# Audio_input_ADC.net
KiCad netlist of a schematic drawn in Altium Designer
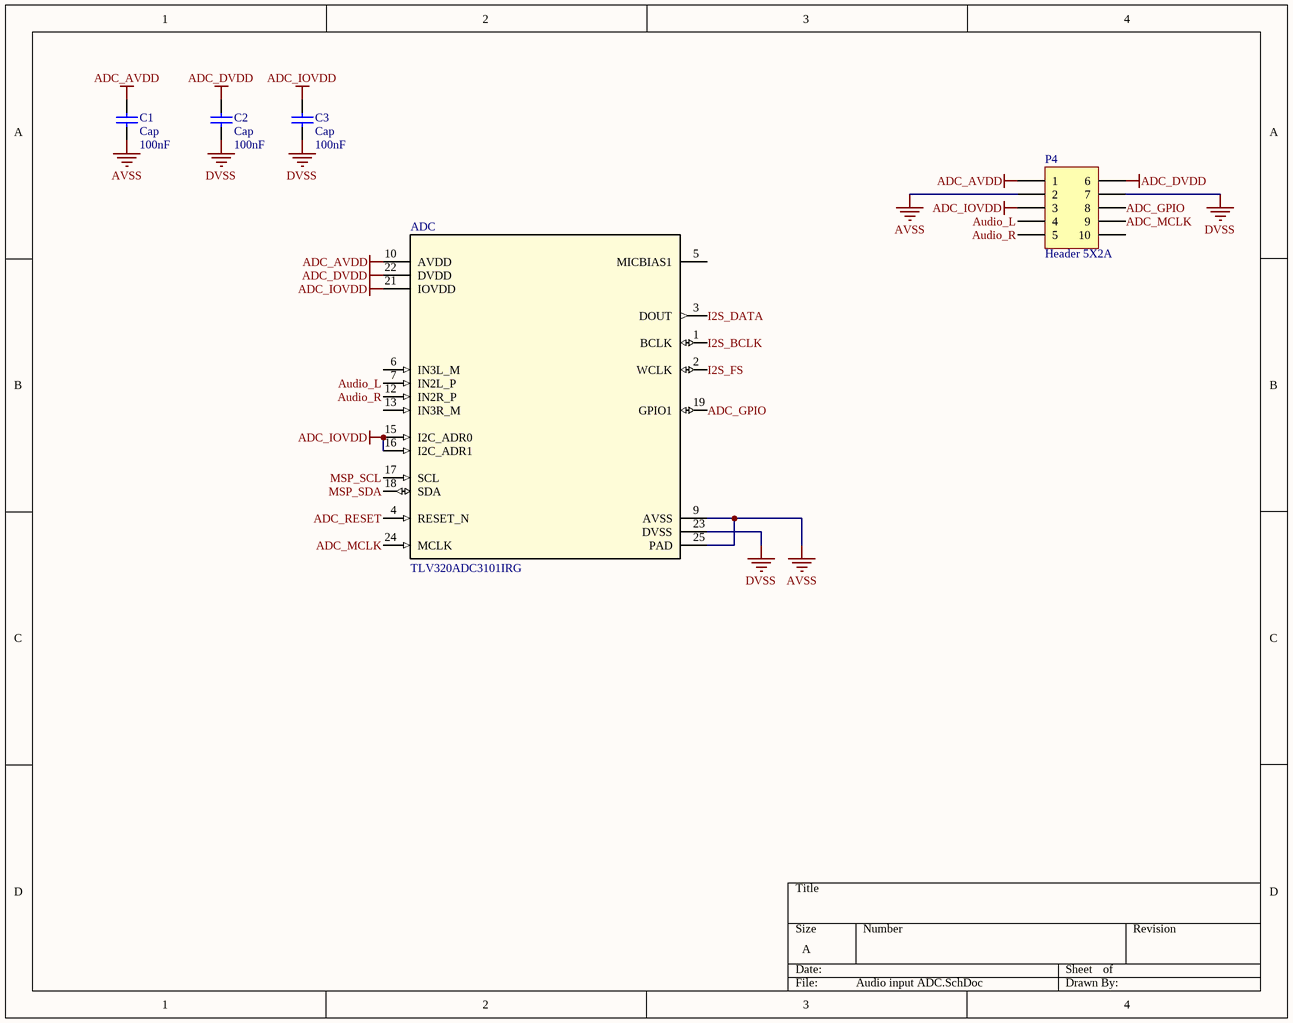
[diagram p0: Audio input ADC.SchDoc]

(export (version "E")
  (design (tool "Eeschema 10.0.6"))
  (components
    (comp (ref "ADC")
      (value "TLV320ADC3101IRG")
      (footprint "RGE0024F_NV")
      (description "Imported")
      (fields
        (field (name "MANUFACTURER") "Texas Instruments")
        (field (name "PARTNUMBER") "TLV320ADC3101IRGER")
      )
      (libsource (lib "2018-10-01_18-58-29") (part "TLV320ADC3101IRG"))
    )
    (comp (ref "C1")
      (value "Cap")
      (footprint "RAD-0.3")
      (description "Capacitor")
      (fields (field (name "ALTIUM_VALUE") "100nF") (field (name "PUBLISHER") "Altium Limited"))
      (libsource (lib "Miscellaneous Devices") (part "Cap"))
    )
    (comp (ref "C2")
      (value "Cap")
      (footprint "RAD-0.3")
      (description "Capacitor")
      (fields (field (name "ALTIUM_VALUE") "100nF") (field (name "PUBLISHER") "Altium Limited"))
      (libsource (lib "Miscellaneous Devices") (part "Cap"))
    )
    (comp (ref "C3")
      (value "Cap")
      (footprint "RAD-0.3")
      (description "Capacitor")
      (fields (field (name "ALTIUM_VALUE") "100nF") (field (name "PUBLISHER") "Altium Limited"))
      (libsource (lib "Miscellaneous Devices") (part "Cap"))
    )
    (comp (ref "P4")
      (value "Header 5X2A")
      (footprint "HDR2X5_CEN")
      (description "Header, 5-Pin, Dual row")
      (fields (field (name "PUBLISHER") "Altium Limited"))
      (libsource (lib "Miscellaneous Connectors") (part "Header 5X2A"))
    )
  )
  (nets
    (net (code "1") (name "/ADC_GPIO") (class "Default")
      (node (ref "ADC") (pin "19") (pinfunction "GPIO1_19") (pintype "bidirectional"))
      (node (ref "P4") (pin "8") (pinfunction "8_8") (pintype "passive"))
    )
    (net (code "2") (name "/ADC_MCLK") (class "Default")
      (node (ref "ADC") (pin "24") (pinfunction "MCLK_24") (pintype "input"))
      (node (ref "P4") (pin "9") (pinfunction "9_9") (pintype "passive"))
    )
    (net (code "3") (name "/ADC_RESET") (class "Default")
      (node (ref "ADC") (pin "4") (pinfunction "RESET_N_4") (pintype "input"))
    )
    (net (code "4") (name "/Audio_L") (class "Default")
      (node (ref "ADC") (pin "7") (pinfunction "IN2L_P_7") (pintype "input"))
      (node (ref "P4") (pin "4") (pinfunction "4_4") (pintype "passive"))
    )
    (net (code "5") (name "/Audio_R") (class "Default")
      (node (ref "ADC") (pin "12") (pinfunction "IN2R_P_12") (pintype "input"))
      (node (ref "P4") (pin "5") (pinfunction "5_5") (pintype "passive"))
    )
    (net (code "6") (name "/I2S_BCLK") (class "Default")
      (node (ref "ADC") (pin "1") (pinfunction "BCLK_1") (pintype "bidirectional"))
    )
    (net (code "7") (name "/I2S_DATA") (class "Default")
      (node (ref "ADC") (pin "3") (pinfunction "DOUT_3") (pintype "output"))
    )
    (net (code "8") (name "/I2S_FS") (class "Default")
      (node (ref "ADC") (pin "2") (pinfunction "WCLK_2") (pintype "bidirectional"))
    )
    (net (code "9") (name "/MSP_SCL") (class "Default")
      (node (ref "ADC") (pin "17") (pinfunction "SCL_17") (pintype "input"))
    )
    (net (code "10") (name "/MSP_SDA") (class "Default")
      (node (ref "ADC") (pin "18") (pinfunction "SDA_18") (pintype "bidirectional"))
    )
    (net (code "11") (name "ADC_AVDD") (class "Default")
      (node (ref "ADC") (pin "10") (pinfunction "AVDD_10") (pintype "power_in"))
      (node (ref "C1") (pin "2") (pinfunction "2_2") (pintype "passive"))
      (node (ref "P4") (pin "1") (pinfunction "1_1") (pintype "passive"))
    )
    (net (code "12") (name "ADC_DVDD") (class "Default")
      (node (ref "ADC") (pin "22") (pinfunction "DVDD_22") (pintype "power_in"))
      (node (ref "C2") (pin "2") (pinfunction "2_2") (pintype "passive"))
      (node (ref "P4") (pin "6") (pinfunction "6_6") (pintype "passive"))
    )
    (net (code "13") (name "ADC_IOVDD") (class "Default")
      (node (ref "ADC") (pin "15") (pinfunction "I2C_ADR0_15") (pintype "input"))
      (node (ref "ADC") (pin "16") (pinfunction "I2C_ADR1_16") (pintype "input"))
      (node (ref "ADC") (pin "21") (pinfunction "IOVDD_21") (pintype "power_in"))
      (node (ref "C3") (pin "2") (pinfunction "2_2") (pintype "passive"))
      (node (ref "P4") (pin "3") (pinfunction "3_3") (pintype "passive"))
    )
    (net (code "14") (name "AVSS") (class "Default")
      (node (ref "ADC") (pin "25") (pinfunction "PAD_25") (pintype "power_in"))
      (node (ref "ADC") (pin "9") (pinfunction "AVSS_9") (pintype "power_in"))
      (node (ref "C1") (pin "1") (pinfunction "1_1") (pintype "passive"))
      (node (ref "P4") (pin "2") (pinfunction "2_2") (pintype "passive"))
    )
    (net (code "15") (name "DVSS") (class "Default")
      (node (ref "ADC") (pin "23") (pinfunction "DVSS_23") (pintype "power_in"))
      (node (ref "C2") (pin "1") (pinfunction "1_1") (pintype "passive"))
      (node (ref "C3") (pin "1") (pinfunction "1_1") (pintype "passive"))
      (node (ref "P4") (pin "7") (pinfunction "7_7") (pintype "passive"))
    )
    (net (code "16") (name "unconnected-(ADC-IN3L_M-Pad6)") (class "Default")
      (node (ref "ADC") (pin "6") (pinfunction "IN3L_M_6") (pintype "input"))
    )
    (net (code "17") (name "unconnected-(ADC-IN3R_M-Pad13)") (class "Default")
      (node (ref "ADC") (pin "13") (pinfunction "IN3R_M_13") (pintype "input"))
    )
    (net (code "18") (name "unconnected-(ADC-MICBIAS1-Pad5)") (class "Default")
      (node (ref "ADC") (pin "5") (pinfunction "MICBIAS1_5") (pintype "power_in"))
    )
    (net (code "19") (name "unconnected-(P4-Pad10)") (class "Default")
      (node (ref "P4") (pin "10") (pinfunction "10_10") (pintype "passive"))
    )
  )
)
